# 150226_AriloTX_REV2_4_0_868MHZ.net
KiCad netlist of a schematic drawn in EAGLE
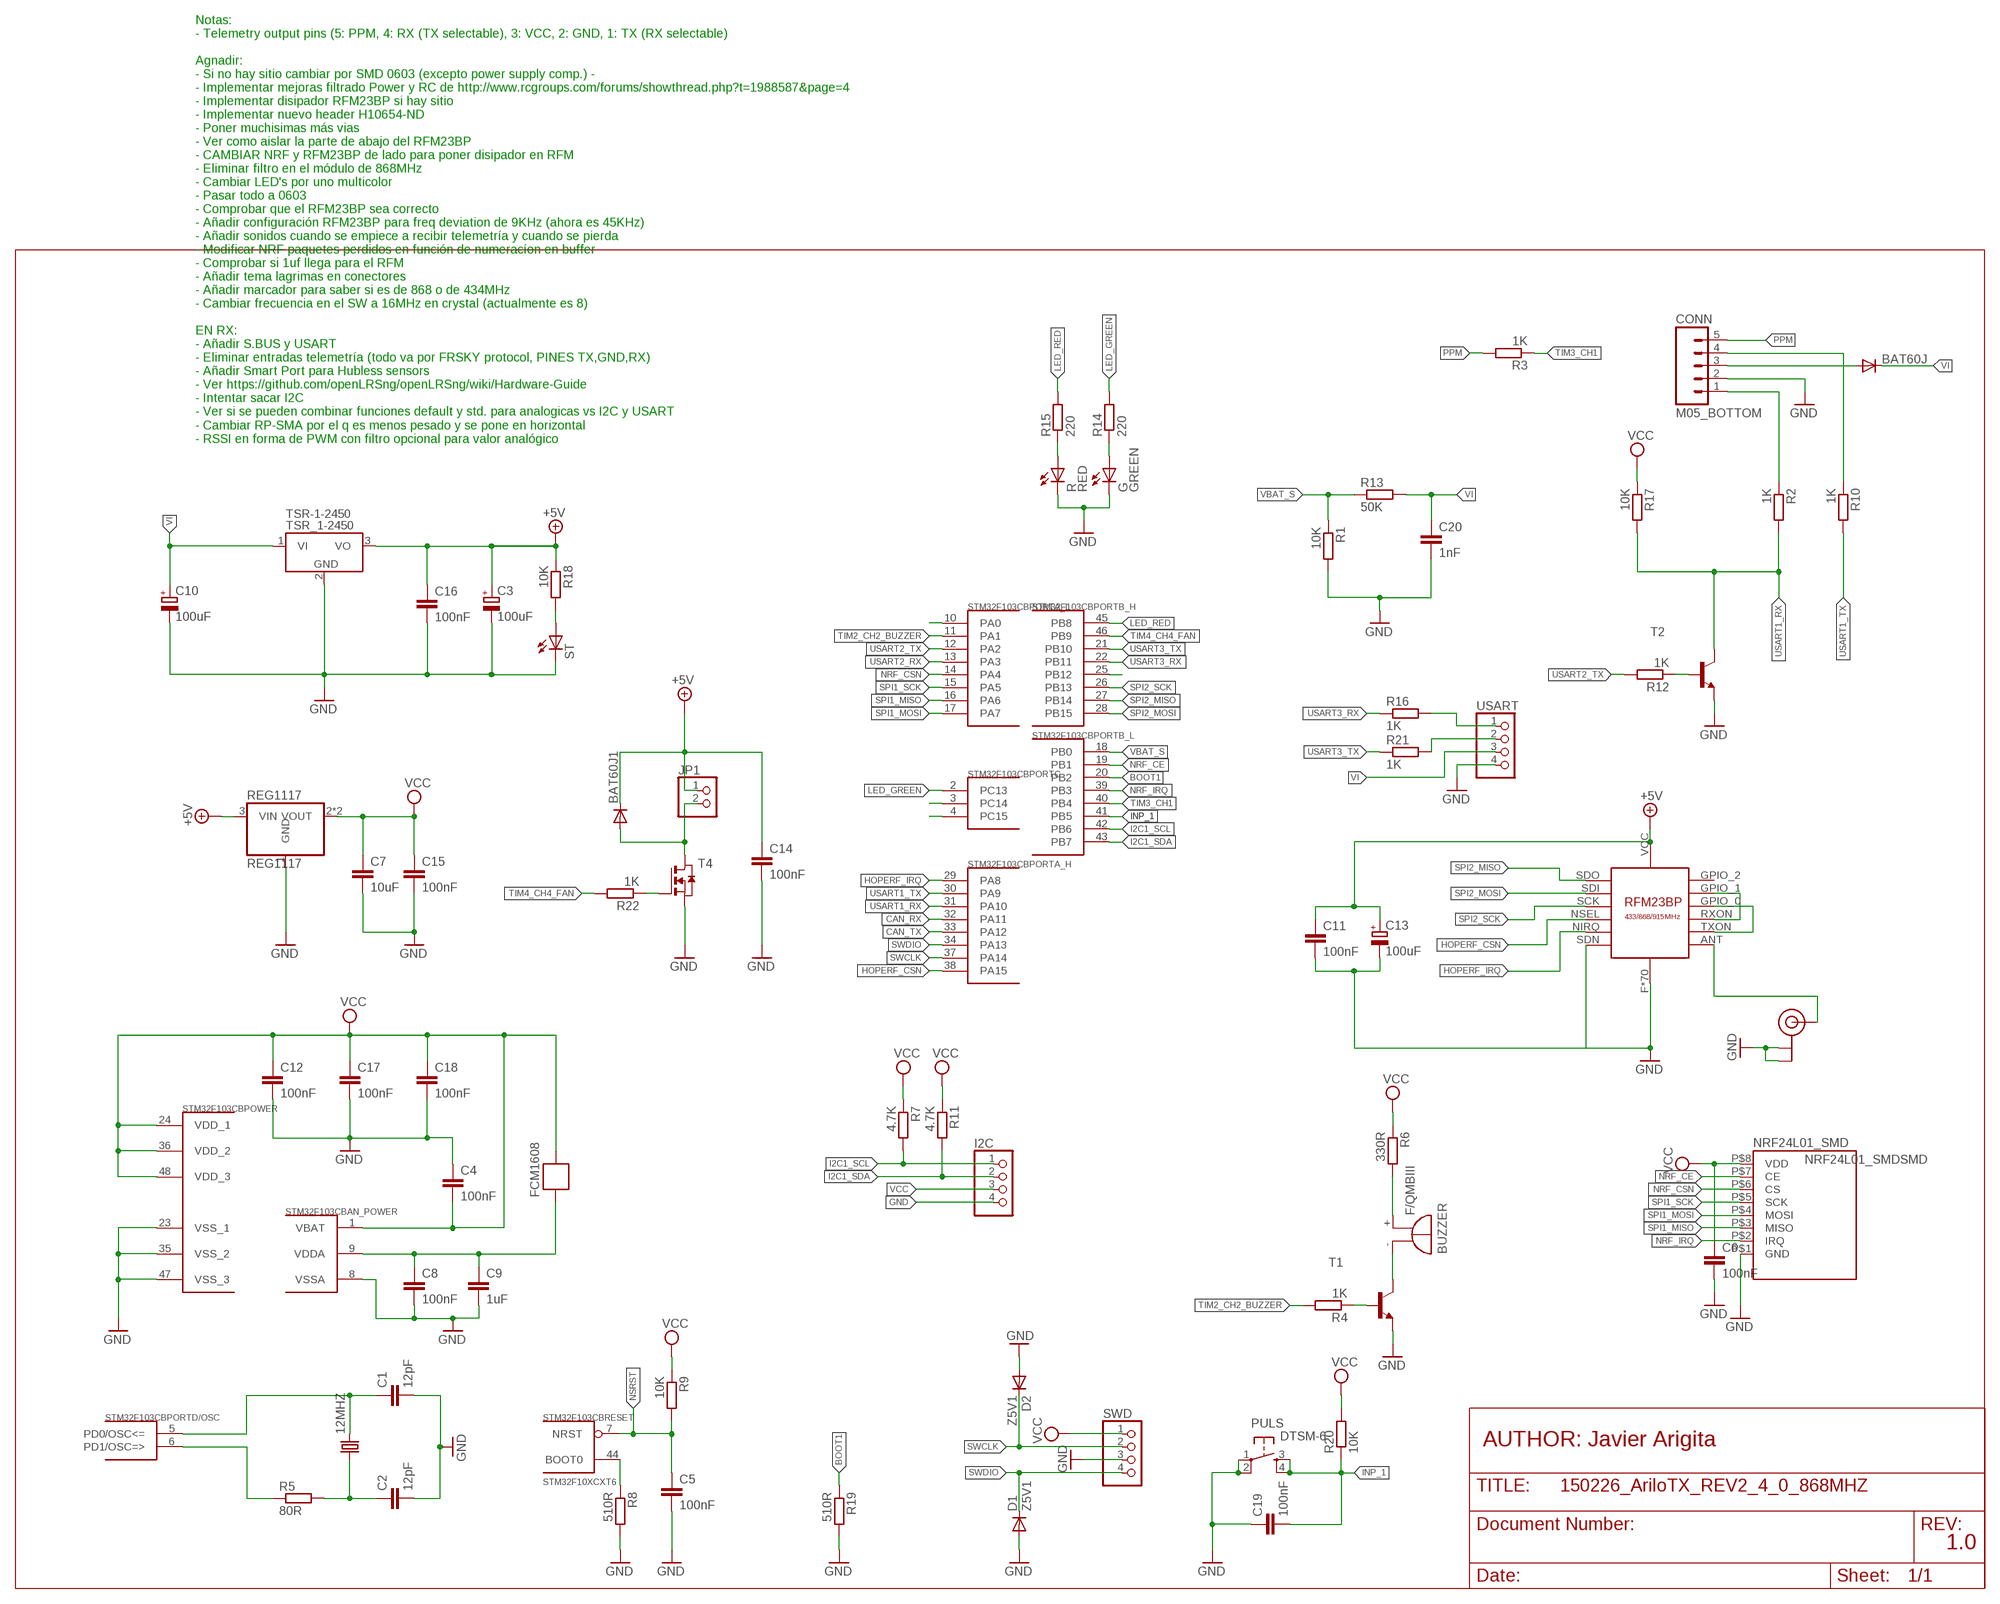
[diagram p0: schematic, sheet 1]

(export (version "E")
  (design (tool "Eeschema 10.0.6"))
  (components
    (comp (ref "12MHZ")
      (value "CRYSTAL5X3")
      (footprint "eagle-import:CRYSTAL-SMD-5X3")
      (libsource (lib "eagle-import") (part "CRYSTAL5X3"))
    )
    (comp (ref "BAT60J")
      (value "DIODE-SOD323-R")
      (footprint "eagle-import:SOD323-R")
      (libsource (lib "eagle-import") (part "DIODE-SOD323-R"))
    )
    (comp (ref "BAT60J1")
      (value "DIODE-SOD323-R")
      (footprint "eagle-import:SOD323-R")
      (libsource (lib "eagle-import") (part "DIODE-SOD323-R"))
    )
    (comp (ref "BUZZER")
      (value "F/QMBIII")
      (footprint "eagle-import:F_QMBIII")
      (libsource (lib "eagle-import") (part "F/QMBIII"))
    )
    (comp (ref "C1")
      (value "12pF")
      (footprint "eagle-import:C0603")
      (libsource (lib "eagle-import") (part "C-EUC0603"))
    )
    (comp (ref "C2")
      (value "12pF")
      (footprint "eagle-import:C0603")
      (libsource (lib "eagle-import") (part "C-EUC0603"))
    )
    (comp (ref "C3")
      (value "100uF")
      (footprint "eagle-import:SMC_B")
      (libsource (lib "eagle-import") (part "CPOL-EUSMCB"))
    )
    (comp (ref "C4")
      (value "100nF")
      (footprint "eagle-import:C0603")
      (libsource (lib "eagle-import") (part "C-EUC0603"))
    )
    (comp (ref "C5")
      (value "100nF")
      (footprint "eagle-import:C0603")
      (libsource (lib "eagle-import") (part "C-EUC0603"))
    )
    (comp (ref "C6")
      (value "100nF")
      (footprint "eagle-import:C0603")
      (libsource (lib "eagle-import") (part "C-EUC0603"))
    )
    (comp (ref "C7")
      (value "10uF")
      (footprint "eagle-import:C0805")
      (libsource (lib "eagle-import") (part "C-EUC0805"))
    )
    (comp (ref "C8")
      (value "100nF")
      (footprint "eagle-import:C0603")
      (libsource (lib "eagle-import") (part "C-EUC0603"))
    )
    (comp (ref "C9")
      (value "1uF")
      (footprint "eagle-import:C0603")
      (libsource (lib "eagle-import") (part "C-EUC0603"))
    )
    (comp (ref "C10")
      (value "100uF")
      (footprint "eagle-import:SMC_B")
      (libsource (lib "eagle-import") (part "CPOL-EUSMCB"))
    )
    (comp (ref "C11")
      (value "100nF")
      (footprint "eagle-import:C0603")
      (libsource (lib "eagle-import") (part "C-EUC0603"))
    )
    (comp (ref "C12")
      (value "100nF")
      (footprint "eagle-import:C0603")
      (libsource (lib "eagle-import") (part "C-EUC0603"))
    )
    (comp (ref "C13")
      (value "100uF")
      (footprint "eagle-import:SMC_B")
      (libsource (lib "eagle-import") (part "CPOL-EUSMCB"))
    )
    (comp (ref "C14")
      (value "100nF")
      (footprint "eagle-import:C0603")
      (libsource (lib "eagle-import") (part "C-EUC0603"))
    )
    (comp (ref "C15")
      (value "100nF")
      (footprint "eagle-import:C0603")
      (libsource (lib "eagle-import") (part "C-EUC0603"))
    )
    (comp (ref "C16")
      (value "100nF")
      (footprint "eagle-import:C0603")
      (libsource (lib "eagle-import") (part "C-EUC0603"))
    )
    (comp (ref "C17")
      (value "100nF")
      (footprint "eagle-import:C0603")
      (libsource (lib "eagle-import") (part "C-EUC0603"))
    )
    (comp (ref "C18")
      (value "100nF")
      (footprint "eagle-import:C0603")
      (libsource (lib "eagle-import") (part "C-EUC0603"))
    )
    (comp (ref "C19")
      (value "100nF")
      (footprint "eagle-import:C0603")
      (libsource (lib "eagle-import") (part "C-EUC0603"))
    )
    (comp (ref "C20")
      (value "1nF")
      (footprint "eagle-import:C0603")
      (libsource (lib "eagle-import") (part "C-EUC0603"))
    )
    (comp (ref "CONN")
      (value "M05_BOTTOM")
      (footprint "eagle-import:M05_BOTTOM")
      (libsource (lib "eagle-import") (part "M05_BOTTOM"))
    )
    (comp (ref "D1")
      (value "Z5V1")
      (footprint "eagle-import:SOD323-R")
      (libsource (lib "eagle-import") (part "DIODE-SOD323-R"))
    )
    (comp (ref "D2")
      (value "Z5V1")
      (footprint "eagle-import:SOD323-R")
      (libsource (lib "eagle-import") (part "DIODE-SOD323-R"))
    )
    (comp (ref "FCM1608")
      (value "FERRITE-BEAD")
      (footprint "eagle-import:R0603")
      (libsource (lib "eagle-import") (part "FERRITE-BEAD"))
    )
    (comp (ref "G")
      (value "GREEN")
      (footprint "eagle-import:CHIP-LED0603")
      (libsource (lib "eagle-import") (part "LEDCHIP-LED0603"))
    )
    (comp (ref "I2C")
      (value "PINHD-1X4")
      (footprint "eagle-import:1X04")
      (libsource (lib "eagle-import") (part "PINHD-1X4"))
    )
    (comp (ref "JP1")
      (value "PINHD-1X2")
      (footprint "eagle-import:1X02")
      (libsource (lib "eagle-import") (part "PINHD-1X2"))
    )
    (comp (ref "NRF24L01_SMD")
      (value "NRF24L01_SMDSMD")
      (footprint "eagle-import:NRF24L01_SMD")
      (libsource (lib "eagle-import") (part "NRF24L01_SMDSMD"))
    )
    (comp (ref "PULS")
      (value "DTSM-6")
      (footprint "eagle-import:DTSM-6")
      (libsource (lib "eagle-import") (part "DTSM-6"))
    )
    (comp (ref "R")
      (value "RED")
      (footprint "eagle-import:CHIP-LED0603")
      (libsource (lib "eagle-import") (part "LEDCHIP-LED0603"))
    )
    (comp (ref "R1")
      (value "10K")
      (footprint "eagle-import:R0603")
      (libsource (lib "eagle-import") (part "R-EU_R0603"))
    )
    (comp (ref "R2")
      (value "1K")
      (footprint "eagle-import:R0603")
      (libsource (lib "eagle-import") (part "R-EU_R0603"))
    )
    (comp (ref "R3")
      (value "1K")
      (footprint "eagle-import:R0603")
      (libsource (lib "eagle-import") (part "R-EU_R0603"))
    )
    (comp (ref "R4")
      (value "1K")
      (footprint "eagle-import:R0603")
      (libsource (lib "eagle-import") (part "R-EU_R0603"))
    )
    (comp (ref "R5")
      (value "80R")
      (footprint "eagle-import:R0603")
      (libsource (lib "eagle-import") (part "R-EU_R0603"))
    )
    (comp (ref "R6")
      (value "330R")
      (footprint "eagle-import:R0603")
      (libsource (lib "eagle-import") (part "R-EU_R0603"))
    )
    (comp (ref "R7")
      (value "4.7K")
      (footprint "eagle-import:R0603")
      (libsource (lib "eagle-import") (part "R-EU_R0603"))
    )
    (comp (ref "R8")
      (value "510R")
      (footprint "eagle-import:R0603")
      (libsource (lib "eagle-import") (part "R-EU_R0603"))
    )
    (comp (ref "R9")
      (value "10K")
      (footprint "eagle-import:R0603")
      (libsource (lib "eagle-import") (part "R-EU_R0603"))
    )
    (comp (ref "R10")
      (value "1K")
      (footprint "eagle-import:R0603")
      (libsource (lib "eagle-import") (part "R-EU_R0603"))
    )
    (comp (ref "R11")
      (value "4.7K")
      (footprint "eagle-import:R0603")
      (libsource (lib "eagle-import") (part "R-EU_R0603"))
    )
    (comp (ref "R12")
      (value "1K")
      (footprint "eagle-import:R0603")
      (libsource (lib "eagle-import") (part "R-EU_R0603"))
    )
    (comp (ref "R13")
      (value "50K")
      (footprint "eagle-import:R0603")
      (libsource (lib "eagle-import") (part "R-EU_R0603"))
    )
    (comp (ref "R14")
      (value "220")
      (footprint "eagle-import:R0603")
      (libsource (lib "eagle-import") (part "R-EU_R0603"))
    )
    (comp (ref "R15")
      (value "220")
      (footprint "eagle-import:R0603")
      (libsource (lib "eagle-import") (part "R-EU_R0603"))
    )
    (comp (ref "R16")
      (value "1K")
      (footprint "eagle-import:R0603")
      (libsource (lib "eagle-import") (part "R-EU_R0603"))
    )
    (comp (ref "R17")
      (value "10K")
      (footprint "eagle-import:R0603")
      (libsource (lib "eagle-import") (part "R-EU_R0603"))
    )
    (comp (ref "R18")
      (value "10K")
      (footprint "eagle-import:R0603")
      (libsource (lib "eagle-import") (part "R-EU_R0603"))
    )
    (comp (ref "R19")
      (value "510R")
      (footprint "eagle-import:R0603")
      (libsource (lib "eagle-import") (part "R-EU_R0603"))
    )
    (comp (ref "R20")
      (value "10K")
      (footprint "eagle-import:R0603")
      (libsource (lib "eagle-import") (part "R-EU_R0603"))
    )
    (comp (ref "R21")
      (value "1K")
      (footprint "eagle-import:R0603")
      (libsource (lib "eagle-import") (part "R-EU_R0603"))
    )
    (comp (ref "R22")
      (value "1K")
      (footprint "eagle-import:R0603")
      (libsource (lib "eagle-import") (part "R-EU_R0603"))
    )
    (comp (ref "REG1117")
      (value "REG1117")
      (footprint "eagle-import:SOT223")
      (libsource (lib "eagle-import") (part "REG1117"))
    )
    (comp (ref "ST")
      (value "LEDCHIP-LED0603")
      (footprint "eagle-import:CHIP-LED0603")
      (libsource (lib "eagle-import") (part "LEDCHIP-LED0603"))
    )
    (comp (ref "STM32F103CB")
      (value "STM32F10XCXT6")
      (footprint "eagle-import:TQFP48")
      (libsource (lib "eagle-import") (part "STM32F10XCXT6"))
    )
    (comp (ref "SWD")
      (value "PINHD-1X4")
      (footprint "eagle-import:1X04")
      (libsource (lib "eagle-import") (part "PINHD-1X4"))
    )
    (comp (ref "T1")
      (value "BC848-NPN-SOT23-BEC")
      (footprint "eagle-import:SOT23-BEC")
      (libsource (lib "eagle-import") (part "-NPN-SOT23-BECBC848"))
    )
    (comp (ref "T2")
      (value "BC848-NPN-SOT23-BEC")
      (footprint "eagle-import:SOT23-BEC")
      (libsource (lib "eagle-import") (part "-NPN-SOT23-BECBC848"))
    )
    (comp (ref "T4")
      (value "NMOSSOT23")
      (footprint "eagle-import:SOT-23")
      (libsource (lib "eagle-import") (part "NMOSSOT23"))
    )
    (comp (ref "TSR-1-2450")
      (value "TSR_1-2450")
      (footprint "eagle-import:TSR-1")
      (libsource (lib "eagle-import") (part "TSR_1-2450"))
    )
    (comp (ref "U$1")
      (value "RFM23BP")
      (footprint "eagle-import:RFM23BP")
      (libsource (lib "eagle-import") (part "RFM23BP"))
    )
    (comp (ref "U.FL")
      (value "U.FL")
      (footprint "eagle-import:U.FL")
      (libsource (lib "eagle-import") (part "U.FL"))
    )
    (comp (ref "USART")
      (value "PINHD-1X4")
      (footprint "eagle-import:1X04")
      (libsource (lib "eagle-import") (part "PINHD-1X4"))
    )
  )
  (nets
    (net (code "1") (name "+5V") (class "Default")
      (node (ref "BAT60J1") (pin "C") (pinfunction "C_C") (pintype "passive"))
      (node (ref "C11") (pin "1") (pinfunction "1_1") (pintype "passive"))
      (node (ref "C13") (pin "+") (pinfunction "+_+") (pintype "passive"))
      (node (ref "C14") (pin "1") (pinfunction "1_1") (pintype "passive"))
      (node (ref "C16") (pin "1") (pinfunction "1_1") (pintype "passive"))
      (node (ref "C3") (pin "+") (pinfunction "+_+") (pintype "passive"))
      (node (ref "JP1") (pin "1") (pinfunction "1_1") (pintype "passive"))
      (node (ref "R18") (pin "1") (pinfunction "1_1") (pintype "passive"))
      (node (ref "REG1117") (pin "3") (pinfunction "VIN_3") (pintype "input"))
      (node (ref "TSR-1-2450") (pin "3") (pinfunction "VO_3") (pintype "power_in"))
      (node (ref "U$1") (pin "VCC") (pinfunction "VCC_VCC") (pintype "power_in"))
    )
    (net (code "2") (name "BOOT1") (class "Default")
      (node (ref "R19") (pin "1") (pinfunction "1_1") (pintype "passive"))
      (node (ref "STM32F103CB") (pin "20") (pinfunction "PB2_20") (pintype "bidirectional"))
    )
    (net (code "3") (name "CAN_RX") (class "Default")
      (node (ref "STM32F103CB") (pin "32") (pinfunction "PA11_32") (pintype "bidirectional"))
    )
    (net (code "4") (name "CAN_TX") (class "Default")
      (node (ref "STM32F103CB") (pin "33") (pinfunction "PA12_33") (pintype "bidirectional"))
    )
    (net (code "5") (name "GND") (class "Default")
      (node (ref "C1") (pin "2") (pinfunction "2_2") (pintype "passive"))
      (node (ref "C10") (pin "-") (pinfunction "-_-") (pintype "passive"))
      (node (ref "C11") (pin "2") (pinfunction "2_2") (pintype "passive"))
      (node (ref "C12") (pin "2") (pinfunction "2_2") (pintype "passive"))
      (node (ref "C13") (pin "-") (pinfunction "-_-") (pintype "passive"))
      (node (ref "C14") (pin "2") (pinfunction "2_2") (pintype "passive"))
      (node (ref "C15") (pin "2") (pinfunction "2_2") (pintype "passive"))
      (node (ref "C16") (pin "2") (pinfunction "2_2") (pintype "passive"))
      (node (ref "C17") (pin "2") (pinfunction "2_2") (pintype "passive"))
      (node (ref "C18") (pin "2") (pinfunction "2_2") (pintype "passive"))
      (node (ref "C19") (pin "1") (pinfunction "1_1") (pintype "passive"))
      (node (ref "C2") (pin "2") (pinfunction "2_2") (pintype "passive"))
      (node (ref "C20") (pin "2") (pinfunction "2_2") (pintype "passive"))
      (node (ref "C3") (pin "-") (pinfunction "-_-") (pintype "passive"))
      (node (ref "C4") (pin "1") (pinfunction "1_1") (pintype "passive"))
      (node (ref "C5") (pin "2") (pinfunction "2_2") (pintype "passive"))
      (node (ref "C6") (pin "2") (pinfunction "2_2") (pintype "passive"))
      (node (ref "C7") (pin "2") (pinfunction "2_2") (pintype "passive"))
      (node (ref "C8") (pin "2") (pinfunction "2_2") (pintype "passive"))
      (node (ref "C9") (pin "2") (pinfunction "2_2") (pintype "passive"))
      (node (ref "CONN") (pin "2") (pinfunction "2_2") (pintype "passive"))
      (node (ref "D1") (pin "A") (pinfunction "A_A") (pintype "passive"))
      (node (ref "D2") (pin "A") (pinfunction "A_A") (pintype "passive"))
      (node (ref "G") (pin "C") (pinfunction "C_C") (pintype "passive"))
      (node (ref "I2C") (pin "4") (pinfunction "4_4") (pintype "passive"))
      (node (ref "NRF24L01_SMD") (pin "P$1") (pinfunction "GND_P$1") (pintype "power_in"))
      (node (ref "PULS") (pin "1") (pinfunction "1_1") (pintype "passive"))
      (node (ref "PULS") (pin "2") (pinfunction "2_2") (pintype "passive"))
      (node (ref "R") (pin "C") (pinfunction "C_C") (pintype "passive"))
      (node (ref "R1") (pin "2") (pinfunction "2_2") (pintype "passive"))
      (node (ref "R19") (pin "2") (pinfunction "2_2") (pintype "passive"))
      (node (ref "R8") (pin "2") (pinfunction "2_2") (pintype "passive"))
      (node (ref "REG1117") (pin "1") (pinfunction "GND_1") (pintype "power_in"))
      (node (ref "ST") (pin "C") (pinfunction "C_C") (pintype "passive"))
      (node (ref "STM32F103CB") (pin "23") (pinfunction "VSS_1_23") (pintype "power_in"))
      (node (ref "STM32F103CB") (pin "35") (pinfunction "VSS_2_35") (pintype "power_in"))
      (node (ref "STM32F103CB") (pin "47") (pinfunction "VSS_3_47") (pintype "power_in"))
      (node (ref "STM32F103CB") (pin "8") (pinfunction "VSSA_8") (pintype "power_in"))
      (node (ref "SWD") (pin "3") (pinfunction "3_3") (pintype "passive"))
      (node (ref "T1") (pin "E") (pinfunction "E_E") (pintype "passive"))
      (node (ref "T2") (pin "E") (pinfunction "E_E") (pintype "passive"))
      (node (ref "T4") (pin "2") (pinfunction "S_2") (pintype "passive"))
      (node (ref "TSR-1-2450") (pin "2") (pinfunction "GND_2") (pintype "power_in"))
      (node (ref "U$1") (pin "F") (pinfunction "GND_F") (pintype "power_in"))
      (node (ref "U$1") (pin "F1") (pinfunction "GND_F1") (pintype "power_in"))
      (node (ref "U$1") (pin "F10") (pinfunction "GND_F10") (pintype "power_in"))
      (node (ref "U$1") (pin "F11") (pinfunction "GND_F11") (pintype "power_in"))
      (node (ref "U$1") (pin "F12") (pinfunction "GND_F12") (pintype "power_in"))
      (node (ref "U$1") (pin "F13") (pinfunction "GND_F13") (pintype "power_in"))
      (node (ref "U$1") (pin "F14") (pinfunction "GND_F14") (pintype "power_in"))
      (node (ref "U$1") (pin "F15") (pinfunction "GND_F15") (pintype "power_in"))
      (node (ref "U$1") (pin "F16") (pinfunction "GND_F16") (pintype "power_in"))
      (node (ref "U$1") (pin "F17") (pinfunction "GND_F17") (pintype "power_in"))
      (node (ref "U$1") (pin "F18") (pinfunction "GND_F18") (pintype "power_in"))
      (node (ref "U$1") (pin "F19") (pinfunction "GND_F19") (pintype "power_in"))
      (node (ref "U$1") (pin "F2") (pinfunction "GND_F2") (pintype "power_in"))
      (node (ref "U$1") (pin "F20") (pinfunction "GND_F20") (pintype "power_in"))
      (node (ref "U$1") (pin "F21") (pinfunction "GND_F21") (pintype "power_in"))
      (node (ref "U$1") (pin "F22") (pinfunction "GND_F22") (pintype "power_in"))
      (node (ref "U$1") (pin "F23") (pinfunction "GND_F23") (pintype "power_in"))
      (node (ref "U$1") (pin "F24") (pinfunction "GND_F24") (pintype "power_in"))
      (node (ref "U$1") (pin "F25") (pinfunction "GND_F25") (pintype "power_in"))
      (node (ref "U$1") (pin "F26") (pinfunction "GND_F26") (pintype "power_in"))
      (node (ref "U$1") (pin "F27") (pinfunction "GND_F27") (pintype "power_in"))
      (node (ref "U$1") (pin "F28") (pinfunction "GND_F28") (pintype "power_in"))
      (node (ref "U$1") (pin "F29") (pinfunction "GND_F29") (pintype "power_in"))
      (node (ref "U$1") (pin "F3") (pinfunction "GND_F3") (pintype "power_in"))
      (node (ref "U$1") (pin "F30") (pinfunction "GND_F30") (pintype "power_in"))
      (node (ref "U$1") (pin "F31") (pinfunction "GND_F31") (pintype "power_in"))
      (node (ref "U$1") (pin "F32") (pinfunction "GND_F32") (pintype "power_in"))
      (node (ref "U$1") (pin "F33") (pinfunction "GND_F33") (pintype "power_in"))
      (node (ref "U$1") (pin "F34") (pinfunction "GND_F34") (pintype "power_in"))
      (node (ref "U$1") (pin "F35") (pinfunction "GND_F35") (pintype "power_in"))
      (node (ref "U$1") (pin "F36") (pinfunction "GND_F36") (pintype "power_in"))
      (node (ref "U$1") (pin "F37") (pinfunction "GND_F37") (pintype "power_in"))
      (node (ref "U$1") (pin "F38") (pinfunction "GND_F38") (pintype "power_in"))
      (node (ref "U$1") (pin "F39") (pinfunction "GND_F39") (pintype "power_in"))
      (node (ref "U$1") (pin "F4") (pinfunction "GND_F4") (pintype "power_in"))
      (node (ref "U$1") (pin "F40") (pinfunction "GND_F40") (pintype "power_in"))
      (node (ref "U$1") (pin "F41") (pinfunction "GND_F41") (pintype "power_in"))
      (node (ref "U$1") (pin "F42") (pinfunction "GND_F42") (pintype "power_in"))
      (node (ref "U$1") (pin "F43") (pinfunction "GND_F43") (pintype "power_in"))
      (node (ref "U$1") (pin "F44") (pinfunction "GND_F44") (pintype "power_in"))
      (node (ref "U$1") (pin "F45") (pinfunction "GND_F45") (pintype "power_in"))
      (node (ref "U$1") (pin "F46") (pinfunction "GND_F46") (pintype "power_in"))
      (node (ref "U$1") (pin "F47") (pinfunction "GND_F47") (pintype "power_in"))
      (node (ref "U$1") (pin "F48") (pinfunction "GND_F48") (pintype "power_in"))
      (node (ref "U$1") (pin "F49") (pinfunction "GND_F49") (pintype "power_in"))
      (node (ref "U$1") (pin "F5") (pinfunction "GND_F5") (pintype "power_in"))
      (node (ref "U$1") (pin "F50") (pinfunction "GND_F50") (pintype "power_in"))
      (node (ref "U$1") (pin "F51") (pinfunction "GND_F51") (pintype "power_in"))
      (node (ref "U$1") (pin "F52") (pinfunction "GND_F52") (pintype "power_in"))
      (node (ref "U$1") (pin "F53") (pinfunction "GND_F53") (pintype "power_in"))
      (node (ref "U$1") (pin "F54") (pinfunction "GND_F54") (pintype "power_in"))
      (node (ref "U$1") (pin "F55") (pinfunction "GND_F55") (pintype "power_in"))
      (node (ref "U$1") (pin "F56") (pinfunction "GND_F56") (pintype "power_in"))
      (node (ref "U$1") (pin "F57") (pinfunction "GND_F57") (pintype "power_in"))
      (node (ref "U$1") (pin "F58") (pinfunction "GND_F58") (pintype "power_in"))
      (node (ref "U$1") (pin "F59") (pinfunction "GND_F59") (pintype "power_in"))
      (node (ref "U$1") (pin "F6") (pinfunction "GND_F6") (pintype "power_in"))
      (node (ref "U$1") (pin "F60") (pinfunction "GND_F60") (pintype "power_in"))
      (node (ref "U$1") (pin "F61") (pinfunction "GND_F61") (pintype "power_in"))
      (node (ref "U$1") (pin "F62") (pinfunction "GND_F62") (pintype "power_in"))
      (node (ref "U$1") (pin "F63") (pinfunction "GND_F63") (pintype "power_in"))
      (node (ref "U$1") (pin "F64") (pinfunction "GND_F64") (pintype "power_in"))
      (node (ref "U$1") (pin "F65") (pinfunction "GND_F65") (pintype "power_in"))
      (node (ref "U$1") (pin "F7") (pinfunction "GND_F7") (pintype "power_in"))
      (node (ref "U$1") (pin "F8") (pinfunction "GND_F8") (pintype "power_in"))
      (node (ref "U$1") (pin "F9") (pinfunction "GND_F9") (pintype "power_in"))
      (node (ref "U$1") (pin "GND1") (pinfunction "GND_GND1") (pintype "power_in"))
      (node (ref "U$1") (pin "GND2") (pinfunction "GND_GND2") (pintype "power_in"))
      (node (ref "U$1") (pin "GND3") (pinfunction "GND_GND3") (pintype "power_in"))
      (node (ref "U$1") (pin "GND_HEAT") (pinfunction "GND_GND_HEAT") (pintype "power_in"))
      (node (ref "U$1") (pin "SDN") (pinfunction "SDN_SDN") (pintype "bidirectional"))
      (node (ref "U.FL") (pin "P$1") (pinfunction "GND_P$1") (pintype "bidirectional"))
      (node (ref "U.FL") (pin "P$2") (pinfunction "GND_P$2") (pintype "bidirectional"))
      (node (ref "USART") (pin "4") (pinfunction "4_4") (pintype "passive"))
    )
    (net (code "6") (name "HOPERF_CSN") (class "Default")
      (node (ref "STM32F103CB") (pin "38") (pinfunction "PA15_38") (pintype "bidirectional"))
      (node (ref "U$1") (pin "NSEL") (pinfunction "NSEL_NSEL") (pintype "bidirectional"))
    )
    (net (code "7") (name "HOPERF_IRQ") (class "Default")
      (node (ref "STM32F103CB") (pin "29") (pinfunction "PA8_29") (pintype "bidirectional"))
      (node (ref "U$1") (pin "NIRQ") (pinfunction "NIRQ_NIRQ") (pintype "bidirectional"))
    )
    (net (code "8") (name "I2C1_SCL") (class "Default")
      (node (ref "I2C") (pin "1") (pinfunction "1_1") (pintype "passive"))
      (node (ref "R7") (pin "2") (pinfunction "2_2") (pintype "passive"))
      (node (ref "STM32F103CB") (pin "42") (pinfunction "PB6_42") (pintype "bidirectional"))
    )
    (net (code "9") (name "I2C1_SDA") (class "Default")
      (node (ref "I2C") (pin "2") (pinfunction "2_2") (pintype "passive"))
      (node (ref "R11") (pin "2") (pinfunction "2_2") (pintype "passive"))
      (node (ref "STM32F103CB") (pin "43") (pinfunction "PB7_43") (pintype "bidirectional"))
    )
    (net (code "10") (name "INP_1") (class "Default")
      (node (ref "C19") (pin "2") (pinfunction "2_2") (pintype "passive"))
      (node (ref "PULS") (pin "3") (pinfunction "3_3") (pintype "passive"))
      (node (ref "PULS") (pin "4") (pinfunction "4_4") (pintype "passive"))
      (node (ref "R20") (pin "1") (pinfunction "1_1") (pintype "passive"))
      (node (ref "STM32F103CB") (pin "41") (pinfunction "PB5_41") (pintype "bidirectional"))
    )
    (net (code "11") (name "LED_GREEN") (class "Default")
      (node (ref "R14") (pin "2") (pinfunction "2_2") (pintype "passive"))
      (node (ref "STM32F103CB") (pin "2") (pinfunction "PC13_2") (pintype "bidirectional"))
    )
    (net (code "12") (name "LED_RED") (class "Default")
      (node (ref "R15") (pin "2") (pinfunction "2_2") (pintype "passive"))
      (node (ref "STM32F103CB") (pin "45") (pinfunction "PB8_45") (pintype "bidirectional"))
    )
    (net (code "13") (name "NRF_CE") (class "Default")
      (node (ref "NRF24L01_SMD") (pin "P$7") (pinfunction "CE_P$7") (pintype "input"))
      (node (ref "STM32F103CB") (pin "19") (pinfunction "PB1_19") (pintype "bidirectional"))
    )
    (net (code "14") (name "NRF_CSN") (class "Default")
      (node (ref "NRF24L01_SMD") (pin "P$6") (pinfunction "CS_P$6") (pintype "input"))
      (node (ref "STM32F103CB") (pin "14") (pinfunction "PA4_14") (pintype "bidirectional"))
    )
    (net (code "15") (name "NRF_IRQ") (class "Default")
      (node (ref "NRF24L01_SMD") (pin "P$2") (pinfunction "IRQ_P$2") (pintype "output"))
      (node (ref "STM32F103CB") (pin "39") (pinfunction "PB3_39") (pintype "bidirectional"))
    )
    (net (code "16") (name "NSRST") (class "Default")
      (node (ref "C5") (pin "1") (pinfunction "1_1") (pintype "passive"))
      (node (ref "R9") (pin "2") (pinfunction "2_2") (pintype "passive"))
      (node (ref "STM32F103CB") (pin "7") (pinfunction "NRST_7") (pintype "input"))
    )
    (net (code "17") (name "Net-(12MHZ-2)") (class "Default")
      (node (ref "12MHZ") (pin "3") (pinfunction "2_3") (pintype "passive"))
      (node (ref "C1") (pin "1") (pinfunction "1_1") (pintype "passive"))
      (node (ref "STM32F103CB") (pin "5") (pinfunction "PD0/OSC<=_5") (pintype "bidirectional"))
    )
    (net (code "18") (name "Net-(12MHZ-Pad1)") (class "Default")
      (node (ref "12MHZ") (pin "1") (pinfunction "1_1") (pintype "passive"))
      (node (ref "C2") (pin "1") (pinfunction "1_1") (pintype "passive"))
      (node (ref "R5") (pin "2") (pinfunction "2_2") (pintype "passive"))
    )
    (net (code "19") (name "Net-(BAT60J-PadA)") (class "Default")
      (node (ref "BAT60J") (pin "A") (pinfunction "A_A") (pintype "passive"))
      (node (ref "CONN") (pin "3") (pinfunction "3_3") (pintype "passive"))
    )
    (net (code "20") (name "Net-(BUZZER-+)") (class "Default")
      (node (ref "BUZZER") (pin "-") (pinfunction "+_-") (pintype "passive"))
      (node (ref "T1") (pin "C") (pinfunction "C_C") (pintype "passive"))
    )
    (net (code "21") (name "Net-(BUZZER--)") (class "Default")
      (node (ref "BUZZER") (pin "+") (pinfunction "-_+") (pintype "passive"))
      (node (ref "R6") (pin "2") (pinfunction "2_2") (pintype "passive"))
    )
    (net (code "22") (name "Net-(CONN-Pad1)") (class "Default")
      (node (ref "CONN") (pin "1") (pinfunction "1_1") (pintype "passive"))
      (node (ref "R2") (pin "1") (pinfunction "1_1") (pintype "passive"))
    )
    (net (code "23") (name "Net-(CONN-Pad4)") (class "Default")
      (node (ref "CONN") (pin "4") (pinfunction "4_4") (pintype "passive"))
      (node (ref "R10") (pin "1") (pinfunction "1_1") (pintype "passive"))
    )
    (net (code "24") (name "Net-(FCM1608-P$2)") (class "Default")
      (node (ref "C8") (pin "1") (pinfunction "1_1") (pintype "passive"))
      (node (ref "C9") (pin "1") (pinfunction "1_1") (pintype "passive"))
      (node (ref "FCM1608") (pin "2") (pinfunction "P$2_2") (pintype "bidirectional"))
      (node (ref "STM32F103CB") (pin "9") (pinfunction "VDDA_9") (pintype "power_in"))
    )
    (net (code "25") (name "Net-(G-PadA)") (class "Default")
      (node (ref "G") (pin "A") (pinfunction "A_A") (pintype "passive"))
      (node (ref "R14") (pin "1") (pinfunction "1_1") (pintype "passive"))
    )
    (net (code "26") (name "Net-(R-PadA)") (class "Default")
      (node (ref "R") (pin "A") (pinfunction "A_A") (pintype "passive"))
      (node (ref "R15") (pin "1") (pinfunction "1_1") (pintype "passive"))
    )
    (net (code "27") (name "Net-(R4-Pad1)") (class "Default")
      (node (ref "R4") (pin "1") (pinfunction "1_1") (pintype "passive"))
      (node (ref "T1") (pin "B") (pinfunction "B_B") (pintype "passive"))
    )
    (net (code "28") (name "Net-(R12-Pad1)") (class "Default")
      (node (ref "R12") (pin "1") (pinfunction "1_1") (pintype "passive"))
      (node (ref "T2") (pin "B") (pinfunction "B_B") (pintype "passive"))
    )
    (net (code "29") (name "Net-(R16-Pad2)") (class "Default")
      (node (ref "R16") (pin "2") (pinfunction "2_2") (pintype "passive"))
      (node (ref "USART") (pin "1") (pinfunction "1_1") (pintype "passive"))
    )
    (net (code "30") (name "Net-(R18-Pad2)") (class "Default")
      (node (ref "R18") (pin "2") (pinfunction "2_2") (pintype "passive"))
      (node (ref "ST") (pin "A") (pinfunction "A_A") (pintype "passive"))
    )
    (net (code "31") (name "Net-(R21-Pad2)") (class "Default")
      (node (ref "R21") (pin "2") (pinfunction "2_2") (pintype "passive"))
      (node (ref "USART") (pin "2") (pinfunction "2_2") (pintype "passive"))
    )
    (net (code "32") (name "Net-(STM32F103CBG-PD1{slash}OSC=>)") (class "Default")
      (node (ref "R5") (pin "1") (pinfunction "1_1") (pintype "passive"))
      (node (ref "STM32F103CB") (pin "6") (pinfunction "PD1/OSC=>_6") (pintype "bidirectional"))
    )
    (net (code "33") (name "Net-(STM32F103CBI-BOOT0)") (class "Default")
      (node (ref "R8") (pin "1") (pinfunction "1_1") (pintype "passive"))
      (node (ref "STM32F103CB") (pin "44") (pinfunction "BOOT0_44") (pintype "input"))
    )
    (net (code "34") (name "Net-(T4-D)") (class "Default")
      (node (ref "BAT60J1") (pin "A") (pinfunction "A_A") (pintype "passive"))
      (node (ref "JP1") (pin "2") (pinfunction "2_2") (pintype "passive"))
      (node (ref "T4") (pin "1") (pinfunction "D_1") (pintype "passive"))
    )
    (net (code "35") (name "Net-(T4-G)") (class "Default")
      (node (ref "R22") (pin "1") (pinfunction "1_1") (pintype "passive"))
      (node (ref "T4") (pin "3") (pinfunction "G_3") (pintype "passive"))
    )
    (net (code "36") (name "Net-(U$1-PadGPIO_0)") (class "Default")
      (node (ref "U$1") (pin "GPIO_0") (pinfunction "GPIO_0_GPIO_0") (pintype "bidirectional"))
      (node (ref "U$1") (pin "TXON") (pinfunction "TXON_TXON") (pintype "bidirectional"))
    )
    (net (code "37") (name "Net-(U$1-PadGPIO_1)") (class "Default")
      (node (ref "U$1") (pin "GPIO_1") (pinfunction "GPIO_1_GPIO_1") (pintype "bidirectional"))
      (node (ref "U$1") (pin "RXON") (pinfunction "RXON_RXON") (pintype "bidirectional"))
    )
    (net (code "38") (name "Net-(U.FL-SIGNAL)") (class "Default")
      (node (ref "U$1") (pin "ANT") (pinfunction "ANT_ANT") (pintype "bidirectional"))
      (node (ref "U.FL") (pin "P$3") (pinfunction "SIGNAL_P$3") (pintype "bidirectional"))
    )
    (net (code "39") (name "PPM") (class "Default")
      (node (ref "CONN") (pin "5") (pinfunction "5_5") (pintype "passive"))
      (node (ref "R3") (pin "2") (pinfunction "2_2") (pintype "passive"))
    )
    (net (code "40") (name "SPI1_MISO") (class "Default")
      (node (ref "NRF24L01_SMD") (pin "P$3") (pinfunction "MISO_P$3") (pintype "output"))
      (node (ref "STM32F103CB") (pin "16") (pinfunction "PA6_16") (pintype "bidirectional"))
    )
    (net (code "41") (name "SPI1_MOSI") (class "Default")
      (node (ref "NRF24L01_SMD") (pin "P$4") (pinfunction "MOSI_P$4") (pintype "input"))
      (node (ref "STM32F103CB") (pin "17") (pinfunction "PA7_17") (pintype "bidirectional"))
    )
    (net (code "42") (name "SPI1_SCK") (class "Default")
      (node (ref "NRF24L01_SMD") (pin "P$5") (pinfunction "SCK_P$5") (pintype "input"))
      (node (ref "STM32F103CB") (pin "15") (pinfunction "PA5_15") (pintype "bidirectional"))
    )
    (net (code "43") (name "SPI2_MISO") (class "Default")
      (node (ref "STM32F103CB") (pin "27") (pinfunction "PB14_27") (pintype "bidirectional"))
      (node (ref "U$1") (pin "SDO") (pinfunction "SDO_SDO") (pintype "bidirectional"))
    )
    (net (code "44") (name "SPI2_MOSI") (class "Default")
      (node (ref "STM32F103CB") (pin "28") (pinfunction "PB15_28") (pintype "bidirectional"))
      (node (ref "U$1") (pin "SDI") (pinfunction "SDI_SDI") (pintype "bidirectional"))
    )
    (net (code "45") (name "SPI2_SCK") (class "Default")
      (node (ref "STM32F103CB") (pin "26") (pinfunction "PB13_26") (pintype "bidirectional"))
      (node (ref "U$1") (pin "SCK") (pinfunction "SCK_SCK") (pintype "bidirectional"))
    )
    (net (code "46") (name "SWCLK") (class "Default")
      (node (ref "D2") (pin "C") (pinfunction "C_C") (pintype "passive"))
      (node (ref "STM32F103CB") (pin "37") (pinfunction "PA14_37") (pintype "bidirectional"))
      (node (ref "SWD") (pin "2") (pinfunction "2_2") (pintype "passive"))
    )
    (net (code "47") (name "SWDIO") (class "Default")
      (node (ref "D1") (pin "C") (pinfunction "C_C") (pintype "passive"))
      (node (ref "STM32F103CB") (pin "34") (pinfunction "PA13_34") (pintype "bidirectional"))
      (node (ref "SWD") (pin "4") (pinfunction "4_4") (pintype "passive"))
    )
    (net (code "48") (name "TIM2_CH2_BUZZER") (class "Default")
      (node (ref "R4") (pin "2") (pinfunction "2_2") (pintype "passive"))
      (node (ref "STM32F103CB") (pin "11") (pinfunction "PA1_11") (pintype "bidirectional"))
    )
    (net (code "49") (name "TIM3_CH1") (class "Default")
      (node (ref "R3") (pin "1") (pinfunction "1_1") (pintype "passive"))
      (node (ref "STM32F103CB") (pin "40") (pinfunction "PB4_40") (pintype "bidirectional"))
    )
    (net (code "50") (name "TIM4_CH4_FAN") (class "Default")
      (node (ref "R22") (pin "2") (pinfunction "2_2") (pintype "passive"))
      (node (ref "STM32F103CB") (pin "46") (pinfunction "PB9_46") (pintype "bidirectional"))
    )
    (net (code "51") (name "USART1_RX") (class "Default")
      (node (ref "R17") (pin "2") (pinfunction "2_2") (pintype "passive"))
      (node (ref "R2") (pin "2") (pinfunction "2_2") (pintype "passive"))
      (node (ref "STM32F103CB") (pin "31") (pinfunction "PA10_31") (pintype "bidirectional"))
      (node (ref "T2") (pin "C") (pinfunction "C_C") (pintype "passive"))
    )
    (net (code "52") (name "USART1_TX") (class "Default")
      (node (ref "R10") (pin "2") (pinfunction "2_2") (pintype "passive"))
      (node (ref "STM32F103CB") (pin "30") (pinfunction "PA9_30") (pintype "bidirectional"))
    )
    (net (code "53") (name "USART2_RX") (class "Default")
      (node (ref "STM32F103CB") (pin "13") (pinfunction "PA3_13") (pintype "bidirectional"))
    )
    (net (code "54") (name "USART2_TX") (class "Default")
      (node (ref "R12") (pin "2") (pinfunction "2_2") (pintype "passive"))
      (node (ref "STM32F103CB") (pin "12") (pinfunction "PA2_12") (pintype "bidirectional"))
    )
    (net (code "55") (name "USART3_RX") (class "Default")
      (node (ref "R16") (pin "1") (pinfunction "1_1") (pintype "passive"))
      (node (ref "STM32F103CB") (pin "22") (pinfunction "PB11_22") (pintype "bidirectional"))
    )
    (net (code "56") (name "USART3_TX") (class "Default")
      (node (ref "R21") (pin "1") (pinfunction "1_1") (pintype "passive"))
      (node (ref "STM32F103CB") (pin "21") (pinfunction "PB10_21") (pintype "bidirectional"))
    )
    (net (code "57") (name "VBAT_S") (class "Default")
      (node (ref "R1") (pin "1") (pinfunction "1_1") (pintype "passive"))
      (node (ref "R13") (pin "1") (pinfunction "1_1") (pintype "passive"))
      (node (ref "STM32F103CB") (pin "18") (pinfunction "PB0_18") (pintype "bidirectional"))
    )
    (net (code "58") (name "VCC") (class "Default")
      (node (ref "C12") (pin "1") (pinfunction "1_1") (pintype "passive"))
      (node (ref "C15") (pin "1") (pinfunction "1_1") (pintype "passive"))
      (node (ref "C17") (pin "1") (pinfunction "1_1") (pintype "passive"))
      (node (ref "C18") (pin "1") (pinfunction "1_1") (pintype "passive"))
      (node (ref "C4") (pin "2") (pinfunction "2_2") (pintype "passive"))
      (node (ref "C6") (pin "1") (pinfunction "1_1") (pintype "passive"))
      (node (ref "C7") (pin "1") (pinfunction "1_1") (pintype "passive"))
      (node (ref "FCM1608") (pin "1") (pinfunction "P$1_1") (pintype "bidirectional"))
      (node (ref "I2C") (pin "3") (pinfunction "3_3") (pintype "passive"))
      (node (ref "NRF24L01_SMD") (pin "P$8") (pinfunction "VDD_P$8") (pintype "bidirectional"))
      (node (ref "R11") (pin "1") (pinfunction "1_1") (pintype "passive"))
      (node (ref "R17") (pin "1") (pinfunction "1_1") (pintype "passive"))
      (node (ref "R20") (pin "2") (pinfunction "2_2") (pintype "passive"))
      (node (ref "R6") (pin "1") (pinfunction "1_1") (pintype "passive"))
      (node (ref "R7") (pin "1") (pinfunction "1_1") (pintype "passive"))
      (node (ref "R9") (pin "1") (pinfunction "1_1") (pintype "passive"))
      (node (ref "REG1117") (pin "2") (pinfunction "VOUT_2") (pintype "power_in"))
      (node (ref "REG1117") (pin "4") (pinfunction "VOUT_4") (pintype "power_in"))
      (node (ref "STM32F103CB") (pin "1") (pinfunction "VBAT_1") (pintype "power_in"))
      (node (ref "STM32F103CB") (pin "24") (pinfunction "VDD_1_24") (pintype "power_in"))
      (node (ref "STM32F103CB") (pin "36") (pinfunction "VDD_2_36") (pintype "power_in"))
      (node (ref "STM32F103CB") (pin "48") (pinfunction "VDD_3_48") (pintype "power_in"))
      (node (ref "SWD") (pin "1") (pinfunction "1_1") (pintype "passive"))
    )
    (net (code "59") (name "VI") (class "Default")
      (node (ref "BAT60J") (pin "C") (pinfunction "C_C") (pintype "passive"))
      (node (ref "C10") (pin "+") (pinfunction "+_+") (pintype "passive"))
      (node (ref "C20") (pin "1") (pinfunction "1_1") (pintype "passive"))
      (node (ref "R13") (pin "2") (pinfunction "2_2") (pintype "passive"))
      (node (ref "TSR-1-2450") (pin "1") (pinfunction "VI_1") (pintype "power_in"))
      (node (ref "USART") (pin "3") (pinfunction "3_3") (pintype "passive"))
    )
    (net (code "60") (name "unconnected-(STM32F103CBC-PA0-Pad10)") (class "Default")
      (node (ref "STM32F103CB") (pin "10") (pinfunction "PA0_10") (pintype "bidirectional"))
    )
    (net (code "61") (name "unconnected-(STM32F103CBD-PB12-Pad25)") (class "Default")
      (node (ref "STM32F103CB") (pin "25") (pinfunction "PB12_25") (pintype "bidirectional"))
    )
    (net (code "62") (name "unconnected-(STM32F103CBF-PC14-Pad3)") (class "Default")
      (node (ref "STM32F103CB") (pin "3") (pinfunction "PC14_3") (pintype "bidirectional"))
    )
    (net (code "63") (name "unconnected-(STM32F103CBF-PC15-Pad4)") (class "Default")
      (node (ref "STM32F103CB") (pin "4") (pinfunction "PC15_4") (pintype "bidirectional"))
    )
    (net (code "64") (name "unconnected-(U$1-PadGPIO_2)") (class "Default")
      (node (ref "U$1") (pin "GPIO_2") (pinfunction "GPIO_2_GPIO_2") (pintype "bidirectional"))
    )
  )
)
